# OpAmp_CCCV_Regulator_2021_09_21_A.net
KiCad netlist of a schematic drawn in EAGLE
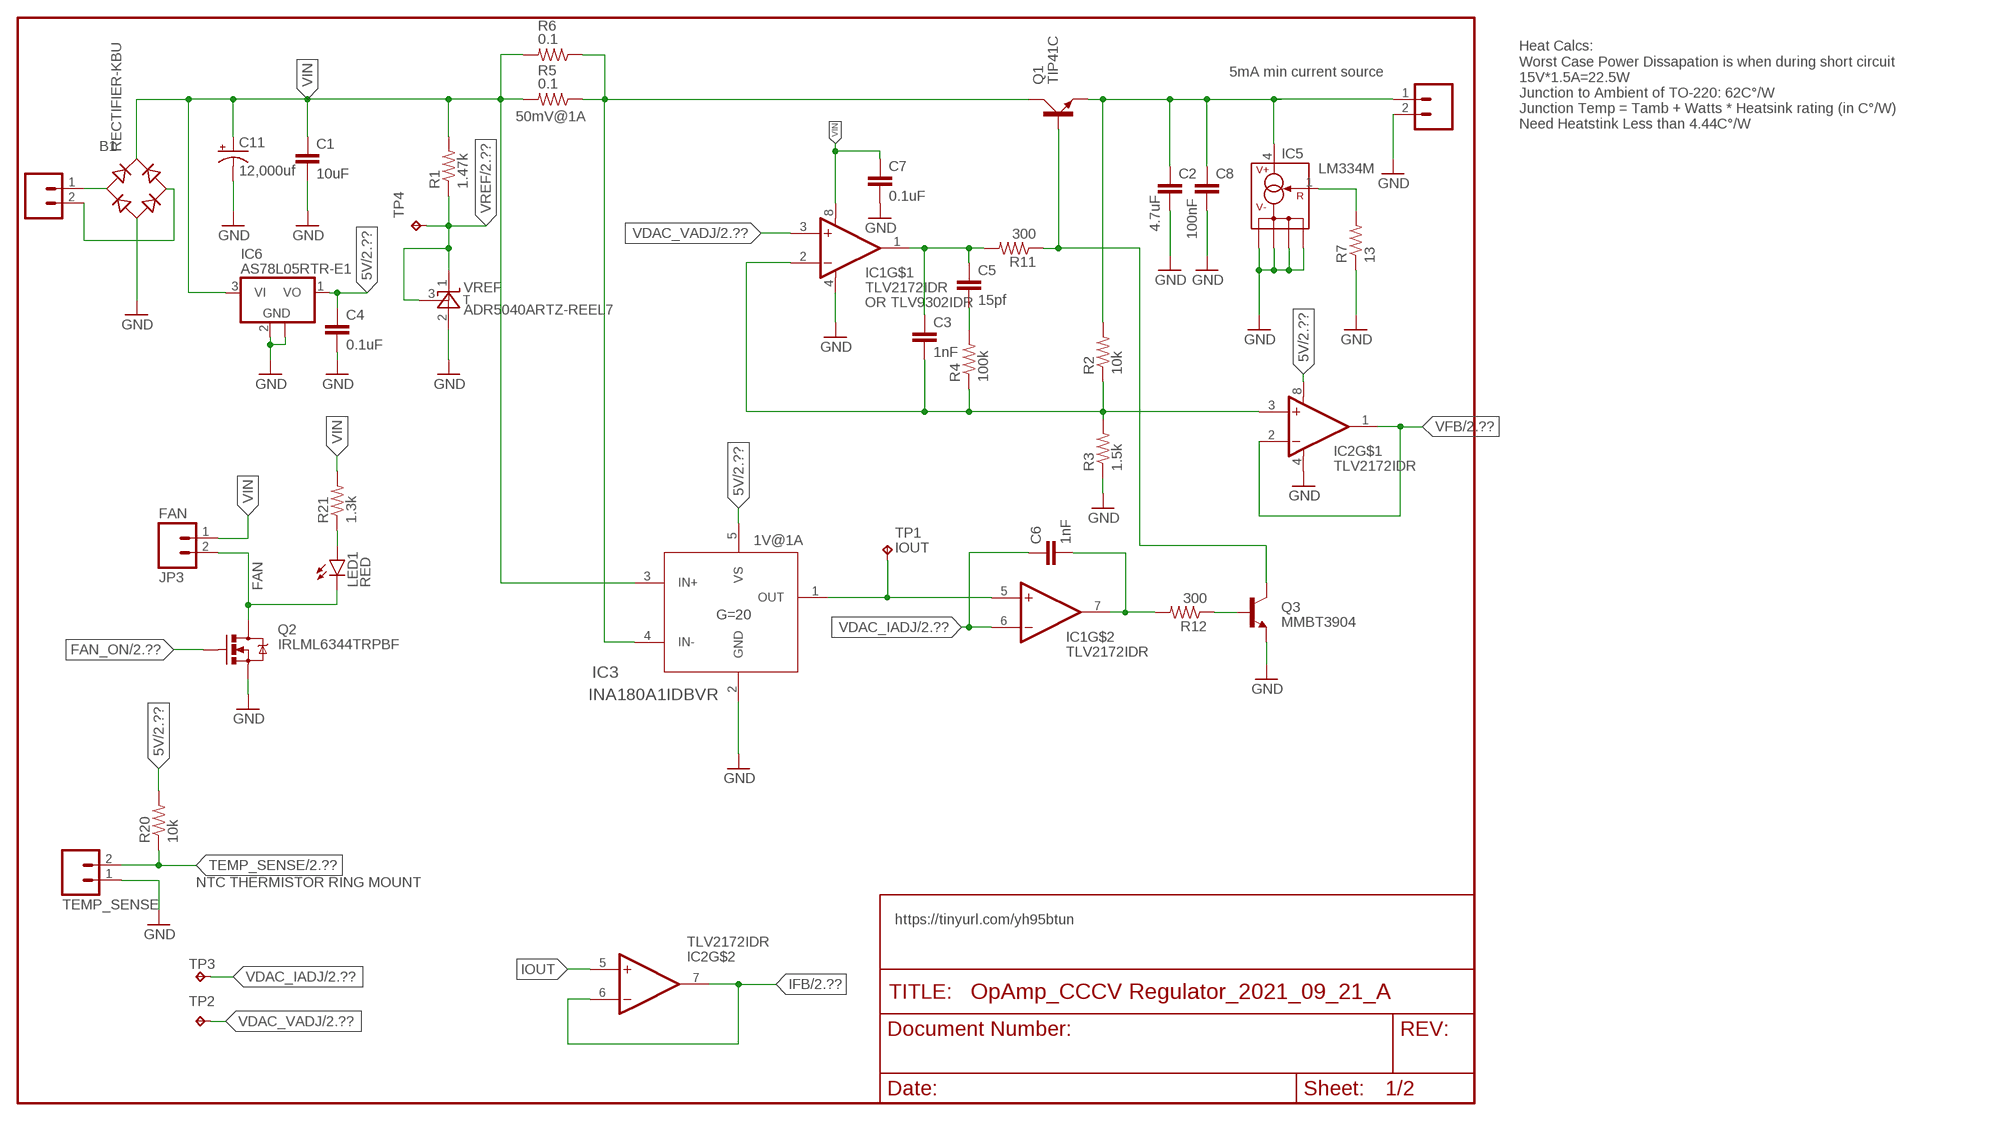
[diagram p0: schematic, sheet 1]
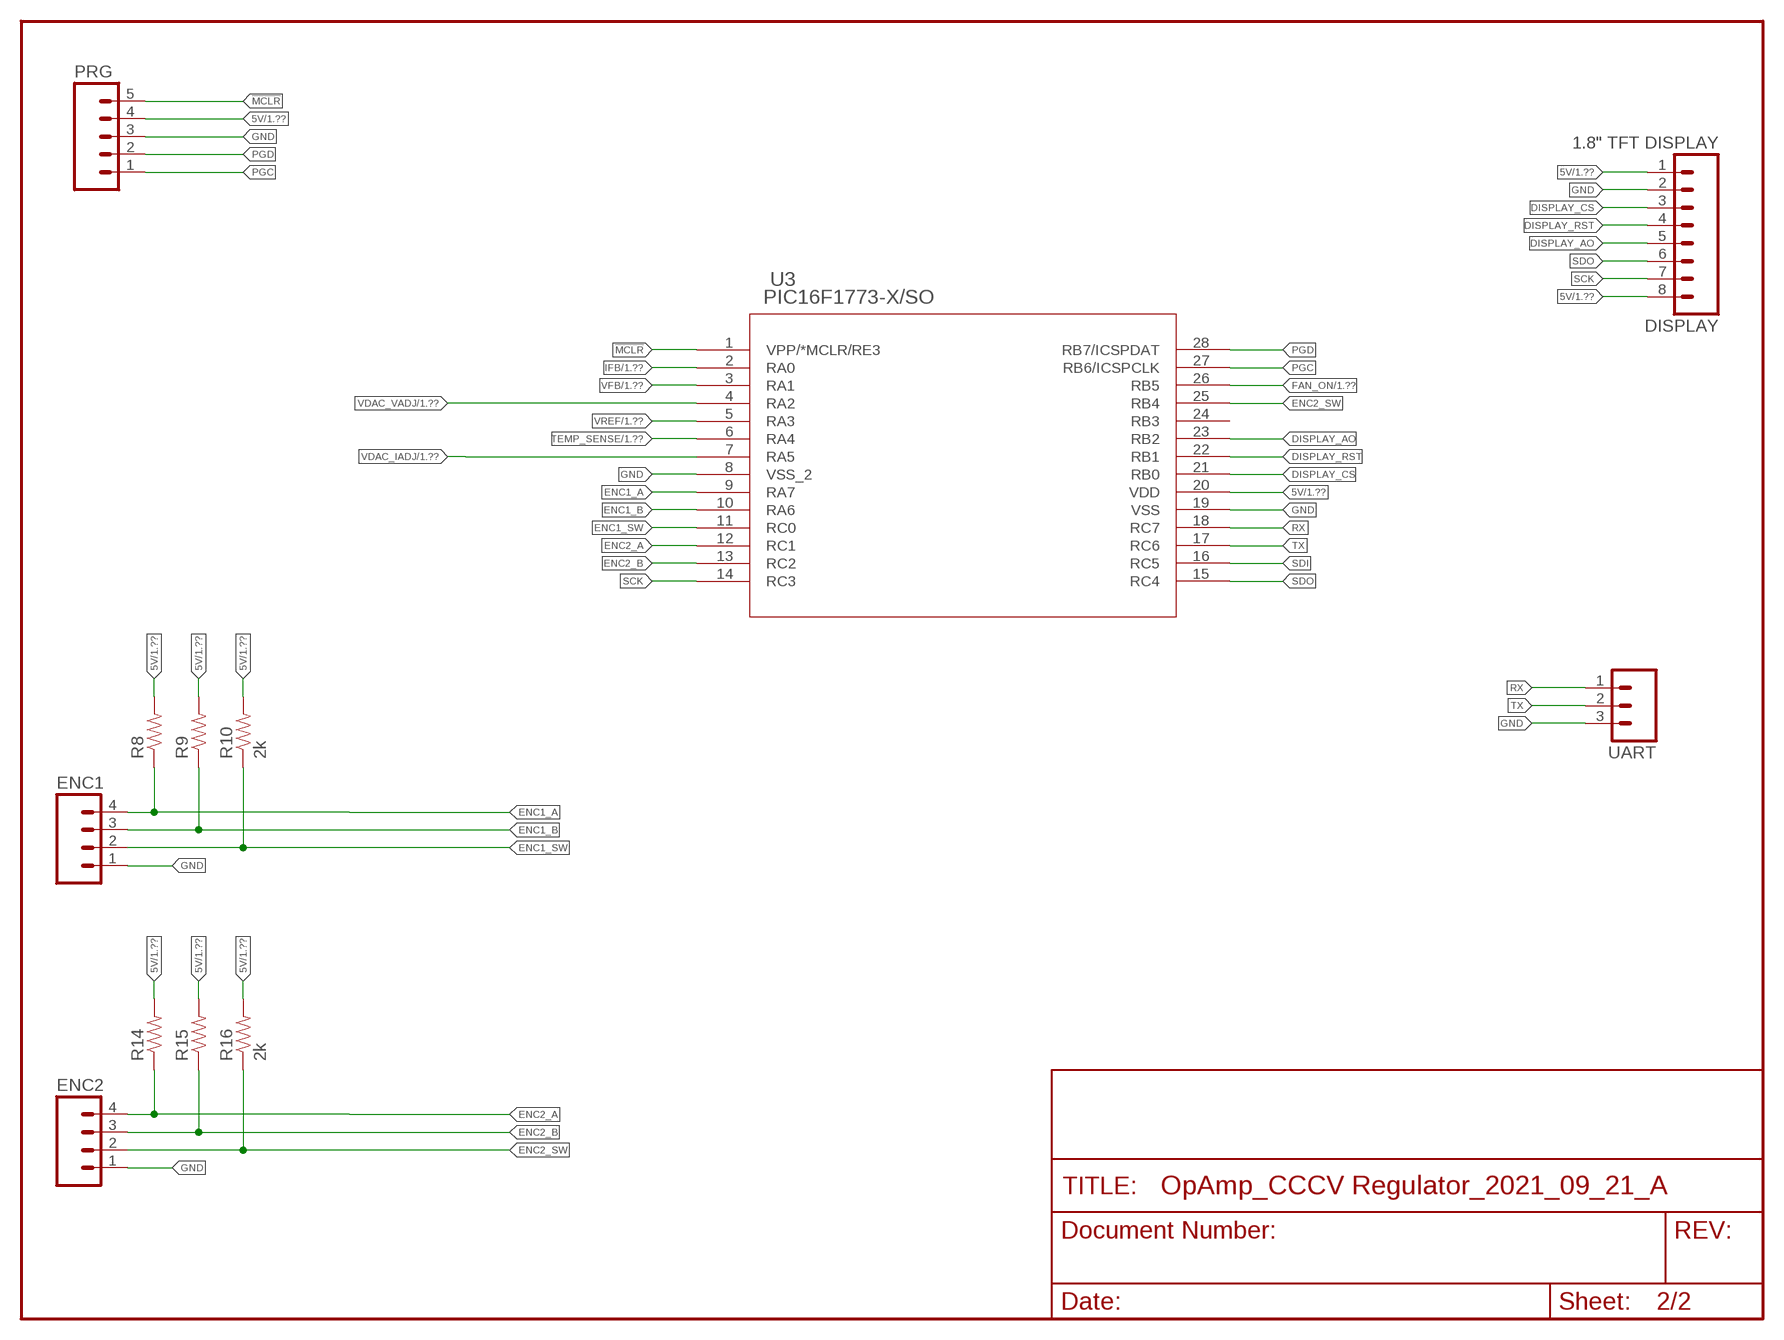
[diagram p1: schematic, sheet 2]

(export (version "E")
  (design (tool "Eeschema 10.0.6"))
  (components
    (comp (ref "DISPLAY")
      (value "1.8\" TFT DISPLAY")
      (footprint "eagle-import:1X08_LOCK_LONGPADS")
      (libsource (lib "eagle-import") (part "M08LOCK_LONGPADS"))
    )
    (comp (ref "ENC1")
      (value "M04LOCK_LONGPADS")
      (footprint "eagle-import:1X04_LOCK_LONGPADS")
      (libsource (lib "eagle-import") (part "M04LOCK_LONGPADS"))
    )
    (comp (ref "ENC2")
      (value "M04LOCK_LONGPADS")
      (footprint "eagle-import:1X04_LOCK_LONGPADS")
      (libsource (lib "eagle-import") (part "M04LOCK_LONGPADS"))
    )
    (comp (ref "PRG")
      (value "M05LOCK")
      (footprint "eagle-import:1X05_LOCK")
      (libsource (lib "eagle-import") (part "M05LOCK"))
    )
    (comp (ref "R8")
      (value "2k")
      (footprint "eagle-import:0805")
      (libsource (lib "eagle-import") (part "SparkFun-Resistors_RESISTOR0805-RES"))
    )
    (comp (ref "R9")
      (value "2k")
      (footprint "eagle-import:0805")
      (libsource (lib "eagle-import") (part "SparkFun-Resistors_RESISTOR0805-RES"))
    )
    (comp (ref "R10")
      (value "2k")
      (footprint "eagle-import:0805")
      (libsource (lib "eagle-import") (part "SparkFun-Resistors_RESISTOR0805-RES"))
    )
    (comp (ref "R14")
      (value "2k")
      (footprint "eagle-import:0805")
      (libsource (lib "eagle-import") (part "SparkFun-Resistors_RESISTOR0805-RES"))
    )
    (comp (ref "R15")
      (value "2k")
      (footprint "eagle-import:0805")
      (libsource (lib "eagle-import") (part "SparkFun-Resistors_RESISTOR0805-RES"))
    )
    (comp (ref "R16")
      (value "2k")
      (footprint "eagle-import:0805")
      (libsource (lib "eagle-import") (part "SparkFun-Resistors_RESISTOR0805-RES"))
    )
    (comp (ref "U3")
      (value "PIC16F1773-X/SO")
      (footprint "eagle-import:SOIC28-W_MC")
      (fields
        (field (name "MANUFACTURER_PART_NUMBER") "pic16f1773-x/so")
        (field (name "COPYRIGHT") "Copyright (C) 2016 Accelerated Designs. All rights reserved")
      )
      (libsource (lib "eagle-import") (part "PIC16F1773-X/SO"))
    )
    (comp (ref "UART")
      (value "M03LOCK_LONGPADS")
      (footprint "eagle-import:1X03_LOCK_LONGPADS")
      (libsource (lib "eagle-import") (part "M03LOCK_LONGPADS"))
    )
    (comp (ref "B1")
      (value "RECTIFIER-KBU")
      (footprint "eagle-import:KBU")
      (libsource (lib "eagle-import") (part "RECTIFIER-KBU"))
    )
    (comp (ref "C1")
      (value "10uF")
      (footprint "eagle-import:1206")
      (libsource (lib "eagle-import") (part "SparkFun-Capacitors_CAP1206"))
    )
    (comp (ref "C2")
      (value "4.7uF")
      (footprint "eagle-import:1206")
      (libsource (lib "eagle-import") (part "SparkFun-Capacitors_CAP1206"))
    )
    (comp (ref "C3")
      (value "1nF")
      (footprint "eagle-import:0805")
      (libsource (lib "eagle-import") (part "CAP0805"))
    )
    (comp (ref "C4")
      (value "0.1uF")
      (footprint "eagle-import:1206")
      (libsource (lib "eagle-import") (part "SparkFun-Capacitors_CAP1206"))
    )
    (comp (ref "C5")
      (value "15pf")
      (footprint "eagle-import:0805")
      (libsource (lib "eagle-import") (part "CAP0805"))
    )
    (comp (ref "C6")
      (value "1nF")
      (footprint "eagle-import:0805")
      (libsource (lib "eagle-import") (part "CAP0805"))
    )
    (comp (ref "C7")
      (value "0.1uF")
      (footprint "eagle-import:0805")
      (libsource (lib "eagle-import") (part "CAP0805"))
    )
    (comp (ref "C8")
      (value "100nF")
      (footprint "eagle-import:1206")
      (libsource (lib "eagle-import") (part "SparkFun-Capacitors_CAP1206"))
    )
    (comp (ref "C11")
      (value "12,000uf")
      (footprint "eagle-import:EB25D")
      (libsource (lib "eagle-import") (part "CPOL-USE10-25"))
    )
    (comp (ref "IC1")
      (value "TLV2172IDR")
      (footprint "eagle-import:SOIC8")
      (libsource (lib "eagle-import") (part "TLV2171IDR"))
    )
    (comp (ref "IC2")
      (value "TLV2172IDR")
      (footprint "eagle-import:SOIC8")
      (libsource (lib "eagle-import") (part "TLV2171IDR"))
    )
    (comp (ref "IC3")
      (value "INA180A1IDBVR")
      (footprint "eagle-import:DBV0005A_N")
      (fields (field (name "MANUFACTURER") "Texas Instruments"))
      (libsource (lib "eagle-import") (part "INA180A1IDBVR"))
    )
    (comp (ref "IC5")
      (value "LM334M")
      (footprint "eagle-import:SO08")
      (libsource (lib "eagle-import") (part "LM334M"))
    )
    (comp (ref "IC6")
      (value "AS78L05RTR-E1")
      (footprint "eagle-import:SOT89")
      (libsource (lib "eagle-import") (part "78LF05"))
    )
    (comp (ref "JP1")
      (value "M023.5MM_LOCK")
      (footprint "eagle-import:SCREWTERMINAL-3.5MM-2_LOCK")
      (libsource (lib "eagle-import") (part "M023.5MM_LOCK"))
    )
    (comp (ref "JP2")
      (value "M023.5MM")
      (footprint "eagle-import:SCREWTERMINAL-3.5MM-2")
      (libsource (lib "eagle-import") (part "M023.5MM"))
    )
    (comp (ref "JP3")
      (value "FAN")
      (footprint "eagle-import:MOLEX-1X2_LOCK")
      (libsource (lib "eagle-import") (part "M02POLAR_LOCK"))
    )
    (comp (ref "JP4")
      (value "TEMP_SENSE")
      (footprint "eagle-import:1X02")
      (libsource (lib "eagle-import") (part "M02PTH"))
    )
    (comp (ref "LED1")
      (value "RED")
      (footprint "eagle-import:LED-1206")
      (libsource (lib "eagle-import") (part "LED1206"))
    )
    (comp (ref "Q1")
      (value "TIP41C")
      (footprint "eagle-import:TO220AV")
      (libsource (lib "eagle-import") (part "TIP41C"))
    )
    (comp (ref "Q2")
      (value "IRLML6344TRPBF")
      (footprint "eagle-import:SOT323")
      (libsource (lib "eagle-import") (part "MOSFET-NCHANNEL2N7002PW"))
    )
    (comp (ref "Q3")
      (value "MMBT3904")
      (footprint "eagle-import:SOT23")
      (libsource (lib "eagle-import") (part "TRANSISTOR_NPNSOT23"))
    )
    (comp (ref "R1")
      (value "1.47k")
      (footprint "eagle-import:1206")
      (libsource (lib "eagle-import") (part "SparkFun-Resistors_RESISTOR1206"))
    )
    (comp (ref "R2")
      (value "10k")
      (footprint "eagle-import:1206")
      (libsource (lib "eagle-import") (part "SparkFun-Resistors_RESISTOR1206"))
    )
    (comp (ref "R3")
      (value "1.5k")
      (footprint "eagle-import:1206")
      (libsource (lib "eagle-import") (part "SparkFun-Resistors_RESISTOR1206"))
    )
    (comp (ref "R4")
      (value "100k")
      (footprint "eagle-import:0805")
      (libsource (lib "eagle-import") (part "RESISTOR0805-RES"))
    )
    (comp (ref "R5")
      (value "0.1")
      (footprint "eagle-import:1206")
      (libsource (lib "eagle-import") (part "SparkFun-Resistors_RESISTOR1206"))
    )
    (comp (ref "R6")
      (value "0.1")
      (footprint "eagle-import:1206")
      (libsource (lib "eagle-import") (part "SparkFun-Resistors_RESISTOR1206"))
    )
    (comp (ref "R7")
      (value "13")
      (footprint "eagle-import:1206")
      (libsource (lib "eagle-import") (part "SparkFun-Resistors_RESISTOR1206"))
    )
    (comp (ref "R11")
      (value "300")
      (footprint "eagle-import:0805")
      (libsource (lib "eagle-import") (part "RESISTOR0805-RES"))
    )
    (comp (ref "R12")
      (value "300")
      (footprint "eagle-import:0805")
      (libsource (lib "eagle-import") (part "RESISTOR0805-RES"))
    )
    (comp (ref "R20")
      (value "10k")
      (footprint "eagle-import:1206")
      (libsource (lib "eagle-import") (part "SparkFun-Resistors_RESISTOR1206"))
    )
    (comp (ref "R21")
      (value "1.3k")
      (footprint "eagle-import:1206")
      (libsource (lib "eagle-import") (part "SparkFun-Resistors_RESISTOR1206"))
    )
    (comp (ref "TP1")
      (value "TPTP20R")
      (footprint "eagle-import:TP20R")
      (libsource (lib "eagle-import") (part "TPTP20R"))
    )
    (comp (ref "TP2")
      (value "TPTP20R")
      (footprint "eagle-import:TP20R")
      (libsource (lib "eagle-import") (part "TPTP20R"))
    )
    (comp (ref "TP3")
      (value "TPTP20R")
      (footprint "eagle-import:TP20R")
      (libsource (lib "eagle-import") (part "TPTP20R"))
    )
    (comp (ref "TP4")
      (value "TPTP20R")
      (footprint "eagle-import:TP20R")
      (libsource (lib "eagle-import") (part "TPTP20R"))
    )
    (comp (ref "VREF")
      (value "ADR5040ARTZ-REEL7")
      (footprint "eagle-import:RT_3_ADI")
      (libsource (lib "eagle-import") (part "ADR5040ARTZ-REEL7"))
    )
  )
  (nets
    (net (code "1") (name "5V") (class "Default")
      (node (ref "C4") (pin "1") (pinfunction "1_1") (pintype "passive"))
      (node (ref "DISPLAY") (pin "1") (pinfunction "1_1") (pintype "passive"))
      (node (ref "DISPLAY") (pin "8") (pinfunction "8_8") (pintype "passive"))
      (node (ref "IC2") (pin "8") (pinfunction "V+_8") (pintype "power_in"))
      (node (ref "IC3") (pin "5") (pinfunction "VS_5") (pintype "power_in"))
      (node (ref "IC6") (pin "1") (pinfunction "VO_1") (pintype "passive"))
      (node (ref "PRG") (pin "4") (pinfunction "4_4") (pintype "passive"))
      (node (ref "R10") (pin "2") (pinfunction "2_2") (pintype "passive"))
      (node (ref "R14") (pin "2") (pinfunction "2_2") (pintype "passive"))
      (node (ref "R15") (pin "2") (pinfunction "2_2") (pintype "passive"))
      (node (ref "R16") (pin "2") (pinfunction "2_2") (pintype "passive"))
      (node (ref "R20") (pin "2") (pinfunction "2_2") (pintype "passive"))
      (node (ref "R8") (pin "2") (pinfunction "2_2") (pintype "passive"))
      (node (ref "R9") (pin "2") (pinfunction "2_2") (pintype "passive"))
      (node (ref "U3") (pin "20") (pinfunction "VDD_20") (pintype "power_in"))
    )
    (net (code "2") (name "DISPLAY_AO") (class "Default")
      (node (ref "DISPLAY") (pin "5") (pinfunction "5_5") (pintype "passive"))
      (node (ref "U3") (pin "23") (pinfunction "RB2_23") (pintype "bidirectional"))
    )
    (net (code "3") (name "DISPLAY_CS") (class "Default")
      (node (ref "DISPLAY") (pin "3") (pinfunction "3_3") (pintype "passive"))
      (node (ref "U3") (pin "21") (pinfunction "RB0_21") (pintype "bidirectional"))
    )
    (net (code "4") (name "DISPLAY_RST") (class "Default")
      (node (ref "DISPLAY") (pin "4") (pinfunction "4_4") (pintype "passive"))
      (node (ref "U3") (pin "22") (pinfunction "RB1_22") (pintype "bidirectional"))
    )
    (net (code "5") (name "ENC1_A") (class "Default")
      (node (ref "ENC1") (pin "4") (pinfunction "4_4") (pintype "passive"))
      (node (ref "R8") (pin "1") (pinfunction "1_1") (pintype "passive"))
      (node (ref "U3") (pin "9") (pinfunction "RA7_9") (pintype "bidirectional"))
    )
    (net (code "6") (name "ENC1_B") (class "Default")
      (node (ref "ENC1") (pin "3") (pinfunction "3_3") (pintype "passive"))
      (node (ref "R9") (pin "1") (pinfunction "1_1") (pintype "passive"))
      (node (ref "U3") (pin "10") (pinfunction "RA6_10") (pintype "bidirectional"))
    )
    (net (code "7") (name "ENC1_SW") (class "Default")
      (node (ref "ENC1") (pin "2") (pinfunction "2_2") (pintype "passive"))
      (node (ref "R10") (pin "1") (pinfunction "1_1") (pintype "passive"))
      (node (ref "U3") (pin "11") (pinfunction "RC0_11") (pintype "bidirectional"))
    )
    (net (code "8") (name "ENC2_A") (class "Default")
      (node (ref "ENC2") (pin "4") (pinfunction "4_4") (pintype "passive"))
      (node (ref "R14") (pin "1") (pinfunction "1_1") (pintype "passive"))
      (node (ref "U3") (pin "12") (pinfunction "RC1_12") (pintype "bidirectional"))
    )
    (net (code "9") (name "ENC2_B") (class "Default")
      (node (ref "ENC2") (pin "3") (pinfunction "3_3") (pintype "passive"))
      (node (ref "R15") (pin "1") (pinfunction "1_1") (pintype "passive"))
      (node (ref "U3") (pin "13") (pinfunction "RC2_13") (pintype "bidirectional"))
    )
    (net (code "10") (name "ENC2_SW") (class "Default")
      (node (ref "ENC2") (pin "2") (pinfunction "2_2") (pintype "passive"))
      (node (ref "R16") (pin "1") (pinfunction "1_1") (pintype "passive"))
      (node (ref "U3") (pin "25") (pinfunction "RB4_25") (pintype "bidirectional"))
    )
    (net (code "11") (name "FAN") (class "Default")
      (node (ref "JP3") (pin "2") (pinfunction "2_2") (pintype "passive"))
      (node (ref "LED1") (pin "C") (pinfunction "C_C") (pintype "passive"))
      (node (ref "Q2") (pin "3") (pinfunction "D_3") (pintype "passive"))
    )
    (net (code "12") (name "FAN_ON") (class "Default")
      (node (ref "Q2") (pin "1") (pinfunction "G_1") (pintype "passive"))
      (node (ref "U3") (pin "26") (pinfunction "RB5_26") (pintype "bidirectional"))
    )
    (net (code "13") (name "GND") (class "Default")
      (node (ref "B1") (pin "-") (pinfunction "-_-") (pintype "passive"))
      (node (ref "C1") (pin "2") (pinfunction "2_2") (pintype "passive"))
      (node (ref "C11") (pin "-") (pinfunction "-_-") (pintype "passive"))
      (node (ref "C2") (pin "2") (pinfunction "2_2") (pintype "passive"))
      (node (ref "C4") (pin "2") (pinfunction "2_2") (pintype "passive"))
      (node (ref "C7") (pin "2") (pinfunction "2_2") (pintype "passive"))
      (node (ref "C8") (pin "2") (pinfunction "2_2") (pintype "passive"))
      (node (ref "DISPLAY") (pin "2") (pinfunction "2_2") (pintype "passive"))
      (node (ref "ENC1") (pin "1") (pinfunction "1_1") (pintype "passive"))
      (node (ref "ENC2") (pin "1") (pinfunction "1_1") (pintype "passive"))
      (node (ref "IC1") (pin "4") (pinfunction "V-_4") (pintype "power_in"))
      (node (ref "IC2") (pin "4") (pinfunction "V-_4") (pintype "power_in"))
      (node (ref "IC3") (pin "2") (pinfunction "GND_2") (pintype "power_in"))
      (node (ref "IC5") (pin "2") (pinfunction "V-_2") (pintype "passive"))
      (node (ref "IC5") (pin "3") (pinfunction "V-_3") (pintype "passive"))
      (node (ref "IC5") (pin "6") (pinfunction "V-_6") (pintype "passive"))
      (node (ref "IC5") (pin "7") (pinfunction "V-_7") (pintype "passive"))
      (node (ref "IC6") (pin "2") (pinfunction "GND_2") (pintype "passive"))
      (node (ref "IC6") (pin "2@1") (pinfunction "GND_2@1") (pintype "passive"))
      (node (ref "JP2") (pin "2") (pinfunction "2_2") (pintype "passive"))
      (node (ref "JP4") (pin "1") (pinfunction "1_1") (pintype "passive"))
      (node (ref "PRG") (pin "3") (pinfunction "3_3") (pintype "passive"))
      (node (ref "Q2") (pin "2") (pinfunction "S_2") (pintype "passive"))
      (node (ref "Q3") (pin "2") (pinfunction "E_2") (pintype "passive"))
      (node (ref "R3") (pin "1") (pinfunction "1_1") (pintype "passive"))
      (node (ref "R7") (pin "1") (pinfunction "1_1") (pintype "passive"))
      (node (ref "U3") (pin "19") (pinfunction "VSS_19") (pintype "power_in"))
      (node (ref "U3") (pin "8") (pinfunction "VSS_2_8") (pintype "power_in"))
      (node (ref "UART") (pin "3") (pinfunction "3_3") (pintype "passive"))
      (node (ref "VREF") (pin "2") (pinfunction "A_2") (pintype "output"))
    )
    (net (code "14") (name "IFB") (class "Default")
      (node (ref "IC2") (pin "6") (pinfunction "-IN_6") (pintype "input"))
      (node (ref "IC2") (pin "7") (pinfunction "OUT_7") (pintype "output"))
      (node (ref "U3") (pin "2") (pinfunction "RA0_2") (pintype "bidirectional"))
    )
    (net (code "15") (name "IOUT") (class "Default")
      (node (ref "IC1") (pin "5") (pinfunction "+IN_5") (pintype "input"))
      (node (ref "IC2") (pin "5") (pinfunction "+IN_5") (pintype "input"))
      (node (ref "IC3") (pin "1") (pinfunction "OUT_1") (pintype "output"))
      (node (ref "TP1") (pin "TP") (pinfunction "TP_TP") (pintype "input"))
    )
    (net (code "16") (name "Net-(B1-PadAC1)") (class "Default")
      (node (ref "B1") (pin "AC1") (pinfunction "AC1_AC1") (pintype "passive"))
      (node (ref "JP1") (pin "1") (pinfunction "1_1") (pintype "passive"))
    )
    (net (code "17") (name "Net-(B1-PadAC2)") (class "Default")
      (node (ref "B1") (pin "AC2") (pinfunction "AC2_AC2") (pintype "passive"))
      (node (ref "JP1") (pin "2") (pinfunction "2_2") (pintype "passive"))
    )
    (net (code "18") (name "Net-(C5-Pad2)") (class "Default")
      (node (ref "C5") (pin "2") (pinfunction "2_2") (pintype "passive"))
      (node (ref "R4") (pin "2") (pinfunction "2_2") (pintype "passive"))
    )
    (net (code "19") (name "Net-(IC1A--IN)") (class "Default")
      (node (ref "C3") (pin "2") (pinfunction "2_2") (pintype "passive"))
      (node (ref "IC1") (pin "2") (pinfunction "-IN_2") (pintype "input"))
      (node (ref "IC2") (pin "3") (pinfunction "+IN_3") (pintype "input"))
      (node (ref "R2") (pin "1") (pinfunction "1_1") (pintype "passive"))
      (node (ref "R3") (pin "2") (pinfunction "2_2") (pintype "passive"))
      (node (ref "R4") (pin "1") (pinfunction "1_1") (pintype "passive"))
    )
    (net (code "20") (name "Net-(IC1A-OUT)") (class "Default")
      (node (ref "C3") (pin "1") (pinfunction "1_1") (pintype "passive"))
      (node (ref "C5") (pin "1") (pinfunction "1_1") (pintype "passive"))
      (node (ref "IC1") (pin "1") (pinfunction "OUT_1") (pintype "output"))
      (node (ref "R11") (pin "2") (pinfunction "2_2") (pintype "passive"))
    )
    (net (code "21") (name "Net-(IC1B-OUT)") (class "Default")
      (node (ref "C6") (pin "2") (pinfunction "2_2") (pintype "passive"))
      (node (ref "IC1") (pin "7") (pinfunction "OUT_7") (pintype "output"))
      (node (ref "R12") (pin "2") (pinfunction "2_2") (pintype "passive"))
    )
    (net (code "22") (name "Net-(IC3-IN-)") (class "Default")
      (node (ref "IC3") (pin "4") (pinfunction "IN-_4") (pintype "input"))
      (node (ref "Q1") (pin "C") (pinfunction "C_C") (pintype "passive"))
      (node (ref "R5") (pin "1") (pinfunction "1_1") (pintype "passive"))
      (node (ref "R6") (pin "1") (pinfunction "1_1") (pintype "passive"))
    )
    (net (code "23") (name "Net-(IC5-R)") (class "Default")
      (node (ref "IC5") (pin "1") (pinfunction "R_1") (pintype "passive"))
      (node (ref "R7") (pin "2") (pinfunction "2_2") (pintype "passive"))
    )
    (net (code "24") (name "Net-(IC5-V+)") (class "Default")
      (node (ref "C2") (pin "1") (pinfunction "1_1") (pintype "passive"))
      (node (ref "C8") (pin "1") (pinfunction "1_1") (pintype "passive"))
      (node (ref "IC5") (pin "4") (pinfunction "V+_4") (pintype "passive"))
      (node (ref "JP2") (pin "1") (pinfunction "1_1") (pintype "passive"))
      (node (ref "Q1") (pin "E") (pinfunction "E_E") (pintype "passive"))
      (node (ref "R2") (pin "2") (pinfunction "2_2") (pintype "passive"))
    )
    (net (code "25") (name "Net-(LED1-PadA)") (class "Default")
      (node (ref "LED1") (pin "A") (pinfunction "A_A") (pintype "passive"))
      (node (ref "R21") (pin "1") (pinfunction "1_1") (pintype "passive"))
    )
    (net (code "26") (name "Net-(Q3-B)") (class "Default")
      (node (ref "Q3") (pin "1") (pinfunction "B_1") (pintype "passive"))
      (node (ref "R12") (pin "1") (pinfunction "1_1") (pintype "passive"))
    )
    (net (code "27") (name "Net-(Q3-C)") (class "Default")
      (node (ref "Q1") (pin "B") (pinfunction "B_B") (pintype "passive"))
      (node (ref "Q3") (pin "3") (pinfunction "C_3") (pintype "passive"))
      (node (ref "R11") (pin "1") (pinfunction "1_1") (pintype "passive"))
    )
    (net (code "28") (name "PGC") (class "Default")
      (node (ref "PRG") (pin "1") (pinfunction "1_1") (pintype "passive"))
      (node (ref "U3") (pin "27") (pinfunction "RB6/ICSPCLK_27") (pintype "bidirectional"))
    )
    (net (code "29") (name "PGD") (class "Default")
      (node (ref "PRG") (pin "2") (pinfunction "2_2") (pintype "passive"))
      (node (ref "U3") (pin "28") (pinfunction "RB7/ICSPDAT_28") (pintype "bidirectional"))
    )
    (net (code "30") (name "RX") (class "Default")
      (node (ref "U3") (pin "18") (pinfunction "RC7_18") (pintype "bidirectional"))
      (node (ref "UART") (pin "1") (pinfunction "1_1") (pintype "passive"))
    )
    (net (code "31") (name "SCK") (class "Default")
      (node (ref "DISPLAY") (pin "7") (pinfunction "7_7") (pintype "passive"))
      (node (ref "U3") (pin "14") (pinfunction "RC3_14") (pintype "bidirectional"))
    )
    (net (code "32") (name "SDI") (class "Default")
      (node (ref "U3") (pin "16") (pinfunction "RC5_16") (pintype "bidirectional"))
    )
    (net (code "33") (name "SDO") (class "Default")
      (node (ref "DISPLAY") (pin "6") (pinfunction "6_6") (pintype "passive"))
      (node (ref "U3") (pin "15") (pinfunction "RC4_15") (pintype "bidirectional"))
    )
    (net (code "34") (name "TEMP_SENSE") (class "Default")
      (node (ref "JP4") (pin "2") (pinfunction "2_2") (pintype "passive"))
      (node (ref "R20") (pin "1") (pinfunction "1_1") (pintype "passive"))
      (node (ref "U3") (pin "6") (pinfunction "RA4_6") (pintype "bidirectional"))
    )
    (net (code "35") (name "TX") (class "Default")
      (node (ref "U3") (pin "17") (pinfunction "RC6_17") (pintype "bidirectional"))
      (node (ref "UART") (pin "2") (pinfunction "2_2") (pintype "passive"))
    )
    (net (code "36") (name "VDAC_IADJ") (class "Default")
      (node (ref "C6") (pin "1") (pinfunction "1_1") (pintype "passive"))
      (node (ref "IC1") (pin "6") (pinfunction "-IN_6") (pintype "input"))
      (node (ref "TP3") (pin "TP") (pinfunction "TP_TP") (pintype "input"))
      (node (ref "U3") (pin "7") (pinfunction "RA5_7") (pintype "bidirectional"))
    )
    (net (code "37") (name "VDAC_VADJ") (class "Default")
      (node (ref "IC1") (pin "3") (pinfunction "+IN_3") (pintype "input"))
      (node (ref "TP2") (pin "TP") (pinfunction "TP_TP") (pintype "input"))
      (node (ref "U3") (pin "4") (pinfunction "RA2_4") (pintype "bidirectional"))
    )
    (net (code "38") (name "VFB") (class "Default")
      (node (ref "IC2") (pin "1") (pinfunction "OUT_1") (pintype "output"))
      (node (ref "IC2") (pin "2") (pinfunction "-IN_2") (pintype "input"))
      (node (ref "U3") (pin "3") (pinfunction "RA1_3") (pintype "bidirectional"))
    )
    (net (code "39") (name "VIN") (class "Default")
      (node (ref "B1") (pin "+") (pinfunction "+_+") (pintype "passive"))
      (node (ref "C1") (pin "1") (pinfunction "1_1") (pintype "passive"))
      (node (ref "C11") (pin "+") (pinfunction "+_+") (pintype "passive"))
      (node (ref "C7") (pin "1") (pinfunction "1_1") (pintype "passive"))
      (node (ref "IC1") (pin "8") (pinfunction "V+_8") (pintype "power_in"))
      (node (ref "IC3") (pin "3") (pinfunction "IN+_3") (pintype "input"))
      (node (ref "IC6") (pin "3") (pinfunction "VI_3") (pintype "input"))
      (node (ref "JP3") (pin "1") (pinfunction "1_1") (pintype "passive"))
      (node (ref "R1") (pin "2") (pinfunction "2_2") (pintype "passive"))
      (node (ref "R21") (pin "2") (pinfunction "2_2") (pintype "passive"))
      (node (ref "R5") (pin "2") (pinfunction "2_2") (pintype "passive"))
      (node (ref "R6") (pin "2") (pinfunction "2_2") (pintype "passive"))
    )
    (net (code "40") (name "VREF") (class "Default")
      (node (ref "R1") (pin "1") (pinfunction "1_1") (pintype "passive"))
      (node (ref "TP4") (pin "TP") (pinfunction "TP_TP") (pintype "input"))
      (node (ref "U3") (pin "5") (pinfunction "RA3_5") (pintype "bidirectional"))
      (node (ref "VREF") (pin "1") (pinfunction "C_1") (pintype "input"))
      (node (ref "VREF") (pin "3") (pinfunction "T_3") (pintype "power_in"))
    )
    (net (code "41") (name "unconnected-(U3-RB3-Pad24)") (class "Default")
      (node (ref "U3") (pin "24") (pinfunction "RB3_24") (pintype "bidirectional"))
    )
    (net (code "42") (name "~{MCLR}") (class "Default")
      (node (ref "PRG") (pin "5") (pinfunction "5_5") (pintype "passive"))
      (node (ref "U3") (pin "1") (pinfunction "VPP/*MCLR/RE3_1") (pintype "bidirectional"))
    )
  )
)
